# BLE-HM10.net
KiCad netlist of a schematic drawn in Altium Designer
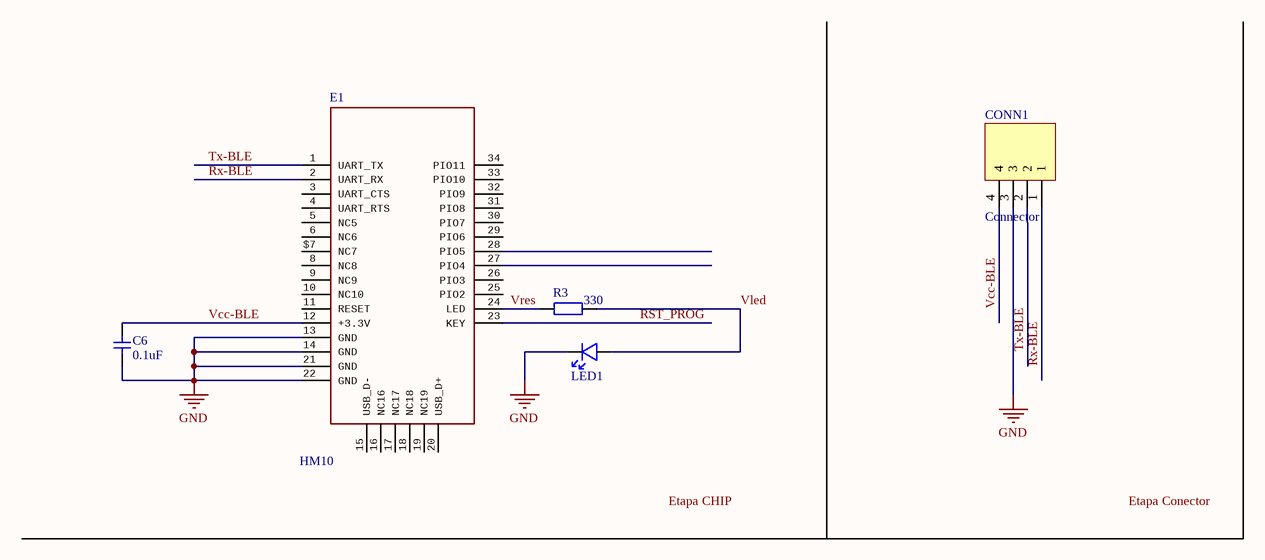
[diagram p0: BLE-HM10.SchDoc]

(export (version "E")
  (design (tool "Eeschema 10.0.6"))
  (components
    (comp (ref "C6")
      (value "0.1uF")
      (footprint "C1206-1.25")
      (description "Capacitor, generic")
      (fields (field (name "Comment") "C2"))
      (libsource (lib "IFS_Altium") (part "C"))
    )
    (comp (ref "CONN1")
      (value "Connector")
      (footprint "1x4x2.54 Pin Header TH V")
      (description "Header")
      (libsource (lib "IFS_Altium") (part "Header 1x4"))
    )
    (comp (ref "E1")
      (value "HM10")
      (footprint "26.9X13X2.2_BOARD")
      (description "HM10 BLE")
      (libsource (lib "JNHuaMao") (part "HM-10-BOARD"))
    )
    (comp (ref "LED1") (value "LED") (footprint "SMT1206-LED") (libsource (lib "LED") (part "LED")))
    (comp (ref "R3")
      (value "330")
      (footprint "R1206-0.55")
      (description "Resistor, generic")
      (fields (field (name "Comment") "R"))
      (libsource (lib "IFS_Altium") (part "R"))
    )
  )
  (nets
    (net (code "3") (name "/RST_PROG") (class "Default")
      (node (ref "E1") (pin "23") (pinfunction "KEY_23") (pintype "passive"))
    )
    (net (code "4") (name "/Rx-BLE") (class "Default")
      (node (ref "CONN1") (pin "1") (pinfunction "1_1") (pintype "passive"))
      (node (ref "E1") (pin "2") (pinfunction "UART_RX_2") (pintype "passive"))
    )
    (net (code "5") (name "/Tx-BLE") (class "Default")
      (node (ref "CONN1") (pin "2") (pinfunction "2_2") (pintype "passive"))
      (node (ref "E1") (pin "1") (pinfunction "UART_TX_1") (pintype "passive"))
    )
    (net (code "6") (name "/Vcc-BLE") (class "Default")
      (node (ref "C6") (pin "2") (pinfunction "2_2") (pintype "passive"))
      (node (ref "CONN1") (pin "4") (pinfunction "4_4") (pintype "passive"))
      (node (ref "E1") (pin "12") (pinfunction "+3.3V_12") (pintype "passive"))
    )
    (net (code "7") (name "/Vled") (class "Default")
      (node (ref "LED1") (pin "1") (pinfunction "1_1") (pintype "passive"))
      (node (ref "R3") (pin "2") (pinfunction "2_2") (pintype "passive"))
    )
    (net (code "8") (name "/Vres") (class "Default")
      (node (ref "E1") (pin "24") (pinfunction "LED_24") (pintype "passive"))
      (node (ref "R3") (pin "1") (pinfunction "1_1") (pintype "passive"))
    )
    (net (code "9") (name "GND") (class "Default")
      (node (ref "C6") (pin "1") (pinfunction "1_1") (pintype "passive"))
      (node (ref "CONN1") (pin "3") (pinfunction "3_3") (pintype "passive"))
      (node (ref "E1") (pin "13") (pinfunction "GND_13") (pintype "passive"))
      (node (ref "E1") (pin "14") (pinfunction "GND_14") (pintype "passive"))
      (node (ref "E1") (pin "21") (pinfunction "GND_21") (pintype "passive"))
      (node (ref "E1") (pin "22") (pinfunction "GND_22") (pintype "passive"))
      (node (ref "LED1") (pin "2") (pinfunction "2_2") (pintype "passive"))
    )
    (net (code "10") (name "unconnected-(E1-NC5-Pad5)") (class "Default")
      (node (ref "E1") (pin "5") (pinfunction "NC5_5") (pintype "passive"))
    )
    (net (code "11") (name "unconnected-(E1-NC6-Pad6)") (class "Default")
      (node (ref "E1") (pin "6") (pinfunction "NC6_6") (pintype "passive"))
    )
    (net (code "12") (name "unconnected-(E1-NC7-Pad$7)") (class "Default")
      (node (ref "E1") (pin "$7") (pinfunction "NC7_$7") (pintype "passive"))
    )
    (net (code "13") (name "unconnected-(E1-NC8-Pad8)") (class "Default")
      (node (ref "E1") (pin "8") (pinfunction "NC8_8") (pintype "passive"))
    )
    (net (code "14") (name "unconnected-(E1-NC9-Pad9)") (class "Default")
      (node (ref "E1") (pin "9") (pinfunction "NC9_9") (pintype "passive"))
    )
    (net (code "15") (name "unconnected-(E1-NC10-Pad10)") (class "Default")
      (node (ref "E1") (pin "10") (pinfunction "NC10_10") (pintype "passive"))
    )
    (net (code "16") (name "unconnected-(E1-NC16-Pad16)") (class "Default")
      (node (ref "E1") (pin "16") (pinfunction "NC16_16") (pintype "passive"))
    )
    (net (code "17") (name "unconnected-(E1-NC17-Pad17)") (class "Default")
      (node (ref "E1") (pin "17") (pinfunction "NC17_17") (pintype "passive"))
    )
    (net (code "18") (name "unconnected-(E1-NC18-Pad18)") (class "Default")
      (node (ref "E1") (pin "18") (pinfunction "NC18_18") (pintype "passive"))
    )
    (net (code "19") (name "unconnected-(E1-NC19-Pad19)") (class "Default")
      (node (ref "E1") (pin "19") (pinfunction "NC19_19") (pintype "passive"))
    )
    (net (code "20") (name "unconnected-(E1-PIO2-Pad25)") (class "Default")
      (node (ref "E1") (pin "25") (pinfunction "PIO2_25") (pintype "passive"))
    )
    (net (code "21") (name "unconnected-(E1-PIO3-Pad26)") (class "Default")
      (node (ref "E1") (pin "26") (pinfunction "PIO3_26") (pintype "passive"))
    )
    (net (code "22") (name "unconnected-(E1-PIO4-Pad27)") (class "Default")
      (node (ref "E1") (pin "27") (pinfunction "PIO4_27") (pintype "passive"))
    )
    (net (code "23") (name "unconnected-(E1-PIO5-Pad28)") (class "Default")
      (node (ref "E1") (pin "28") (pinfunction "PIO5_28") (pintype "passive"))
    )
    (net (code "24") (name "unconnected-(E1-PIO6-Pad29)") (class "Default")
      (node (ref "E1") (pin "29") (pinfunction "PIO6_29") (pintype "passive"))
    )
    (net (code "25") (name "unconnected-(E1-PIO7-Pad30)") (class "Default")
      (node (ref "E1") (pin "30") (pinfunction "PIO7_30") (pintype "passive"))
    )
    (net (code "26") (name "unconnected-(E1-PIO8-Pad31)") (class "Default")
      (node (ref "E1") (pin "31") (pinfunction "PIO8_31") (pintype "passive"))
    )
    (net (code "27") (name "unconnected-(E1-PIO9-Pad32)") (class "Default")
      (node (ref "E1") (pin "32") (pinfunction "PIO9_32") (pintype "passive"))
    )
    (net (code "28") (name "unconnected-(E1-PIO10-Pad33)") (class "Default")
      (node (ref "E1") (pin "33") (pinfunction "PIO10_33") (pintype "passive"))
    )
    (net (code "29") (name "unconnected-(E1-PIO11-Pad34)") (class "Default")
      (node (ref "E1") (pin "34") (pinfunction "PIO11_34") (pintype "passive"))
    )
    (net (code "30") (name "unconnected-(E1-RESET-Pad11)") (class "Default")
      (node (ref "E1") (pin "11") (pinfunction "RESET_11") (pintype "passive"))
    )
    (net (code "31") (name "unconnected-(E1-UART_CTS-Pad3)") (class "Default")
      (node (ref "E1") (pin "3") (pinfunction "UART_CTS_3") (pintype "passive"))
    )
    (net (code "32") (name "unconnected-(E1-UART_RTS-Pad4)") (class "Default")
      (node (ref "E1") (pin "4") (pinfunction "UART_RTS_4") (pintype "passive"))
    )
    (net (code "33") (name "unconnected-(E1-USB_D+-Pad20)") (class "Default")
      (node (ref "E1") (pin "20") (pinfunction "USB_D+_20") (pintype "passive"))
    )
    (net (code "34") (name "unconnected-(E1-USB_D--Pad15)") (class "Default")
      (node (ref "E1") (pin "15") (pinfunction "USB_D-_15") (pintype "passive"))
    )
  )
)
